# Sheet3.net
KiCad netlist of a schematic drawn in Altium Designer
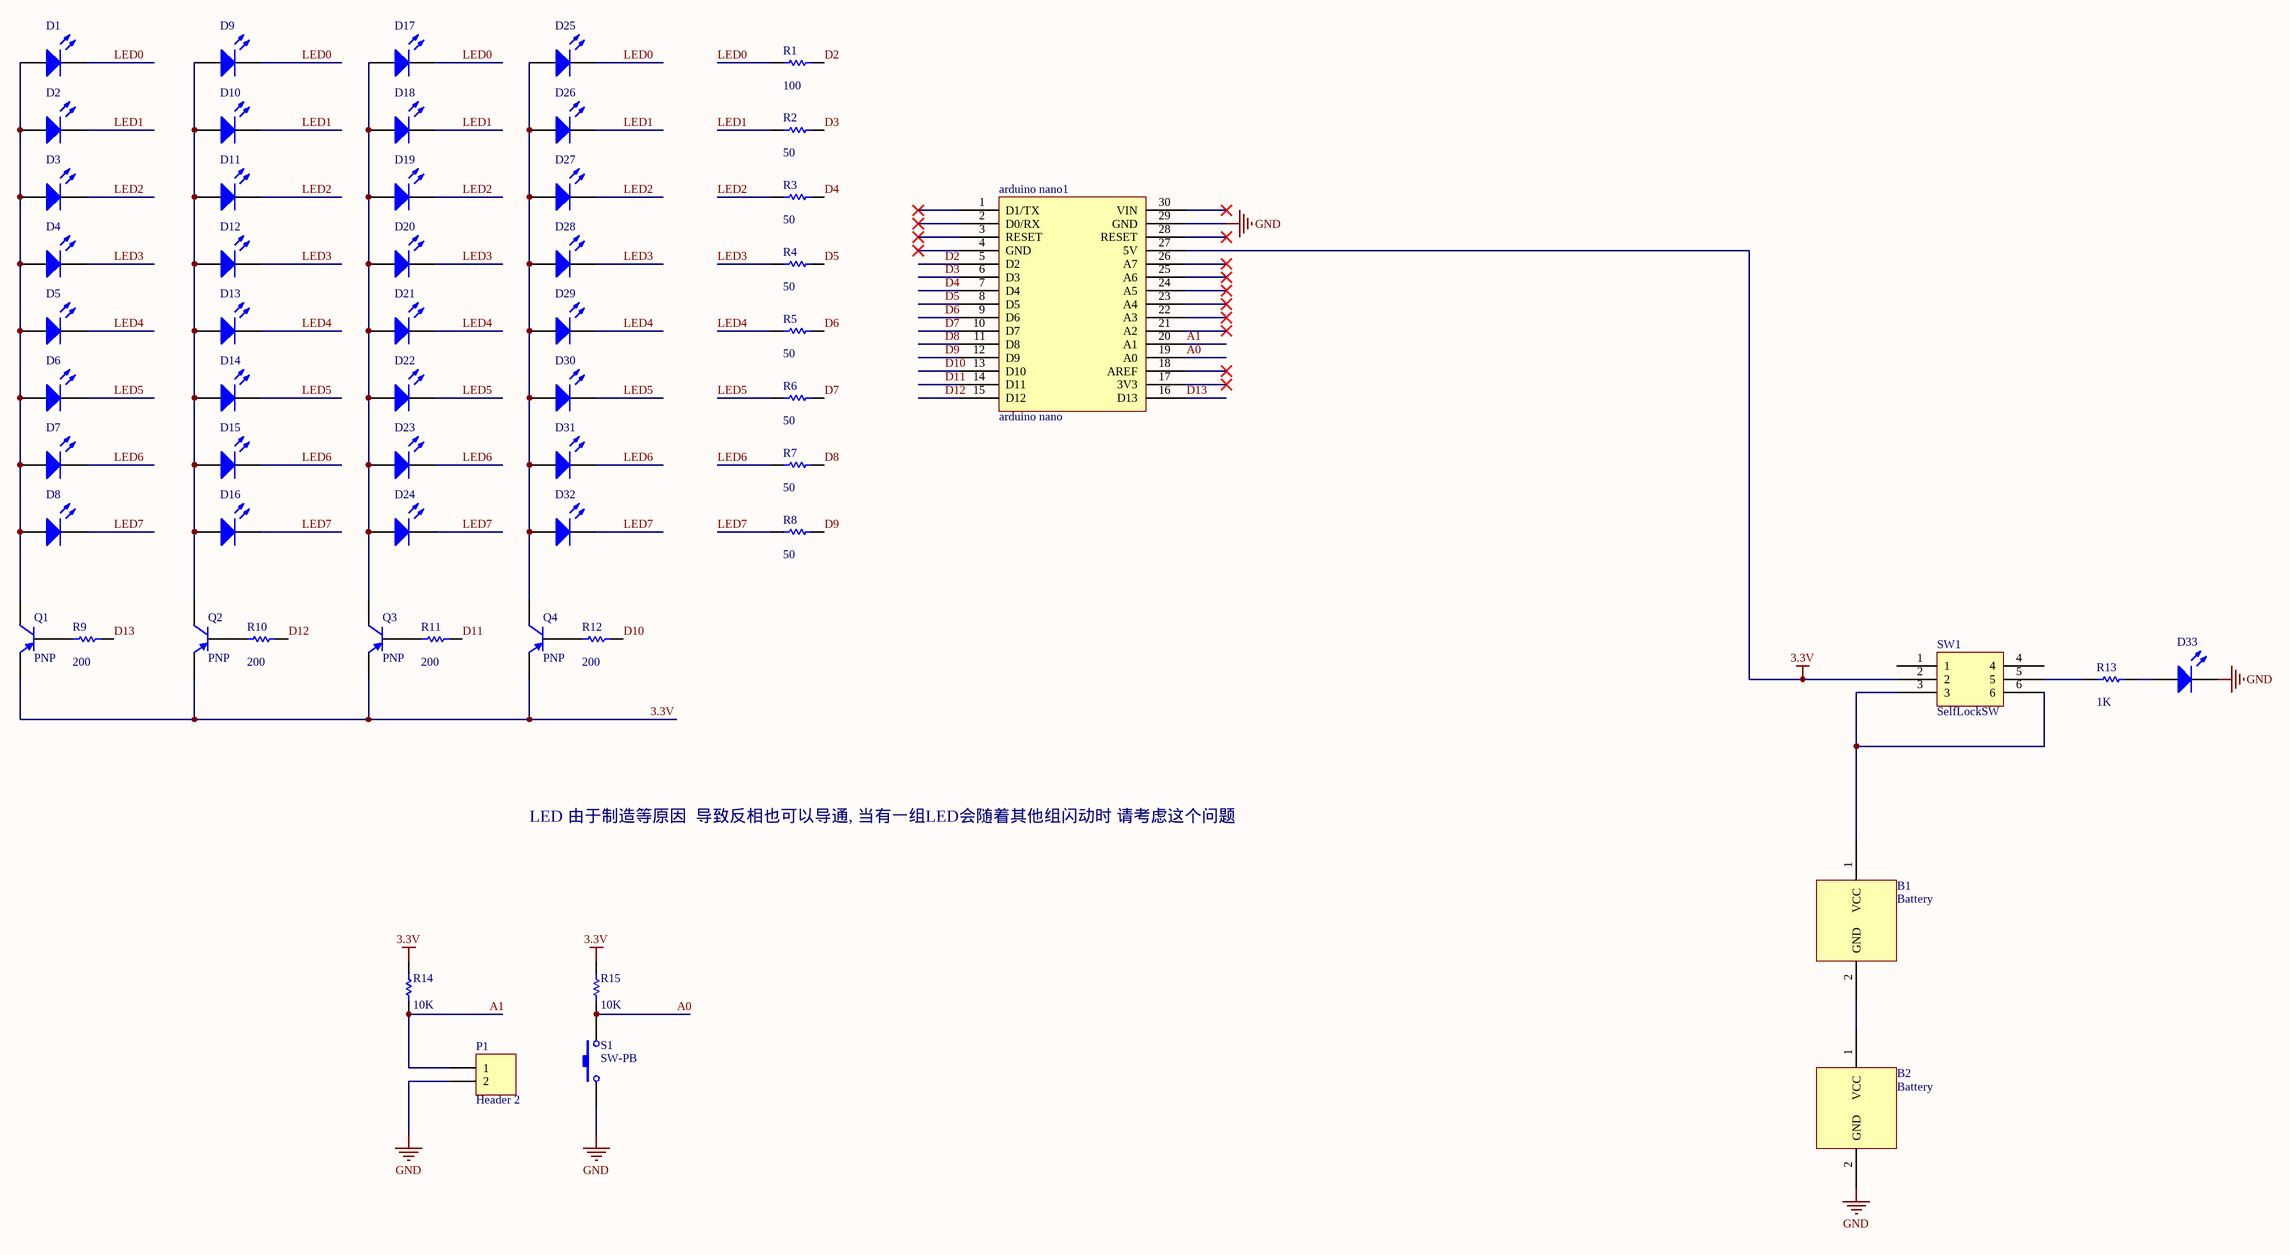
[diagram p0: Sheet3.SchDoc]

(export (version "E")
  (design (tool "Eeschema 10.0.6"))
  (components
    (comp (ref "arduino nano1")
      (value "arduino nano")
      (footprint "PcbLib1:arduino nano - duplicate")
      (libsource (lib "Schlib1") (part "arduino"))
    )
    (comp (ref "B1")
      (value "Battery")
      (footprint "PcbLib1:battery")
      (libsource (lib "Schlib1") (part "Battery"))
    )
    (comp (ref "B2")
      (value "Battery")
      (footprint "PcbLib1:battery")
      (libsource (lib "Schlib1") (part "Battery"))
    )
    (comp (ref "D1")
      (value "LED3")
      (footprint "3.5X2.8X1.9")
      (description "Typical BLUE SiC LED")
      (fields (field (name "PUBLISHER") "Altium Limited"))
      (libsource (lib "Miscellaneous Devices") (part "LED3"))
    )
    (comp (ref "D2")
      (value "LED3")
      (footprint "3.5X2.8X1.9")
      (description "Typical BLUE SiC LED")
      (fields (field (name "PUBLISHER") "Altium Limited"))
      (libsource (lib "Miscellaneous Devices") (part "LED3"))
    )
    (comp (ref "D3")
      (value "LED3")
      (footprint "3.5X2.8X1.9")
      (description "Typical BLUE SiC LED")
      (fields (field (name "PUBLISHER") "Altium Limited"))
      (libsource (lib "Miscellaneous Devices") (part "LED3"))
    )
    (comp (ref "D4")
      (value "LED3")
      (footprint "3.5X2.8X1.9")
      (description "Typical BLUE SiC LED")
      (fields (field (name "PUBLISHER") "Altium Limited"))
      (libsource (lib "Miscellaneous Devices") (part "LED3"))
    )
    (comp (ref "D5")
      (value "LED3")
      (footprint "3.5X2.8X1.9")
      (description "Typical BLUE SiC LED")
      (fields (field (name "PUBLISHER") "Altium Limited"))
      (libsource (lib "Miscellaneous Devices") (part "LED3"))
    )
    (comp (ref "D6")
      (value "LED3")
      (footprint "3.5X2.8X1.9")
      (description "Typical BLUE SiC LED")
      (fields (field (name "PUBLISHER") "Altium Limited"))
      (libsource (lib "Miscellaneous Devices") (part "LED3"))
    )
    (comp (ref "D7")
      (value "LED3")
      (footprint "3.5X2.8X1.9")
      (description "Typical BLUE SiC LED")
      (fields (field (name "PUBLISHER") "Altium Limited"))
      (libsource (lib "Miscellaneous Devices") (part "LED3"))
    )
    (comp (ref "D8")
      (value "LED3")
      (footprint "3.5X2.8X1.9")
      (description "Typical BLUE SiC LED")
      (fields (field (name "PUBLISHER") "Altium Limited"))
      (libsource (lib "Miscellaneous Devices") (part "LED3"))
    )
    (comp (ref "D9")
      (value "LED3")
      (footprint "3.5X2.8X1.9")
      (description "Typical BLUE SiC LED")
      (fields (field (name "PUBLISHER") "Altium Limited"))
      (libsource (lib "Miscellaneous Devices") (part "LED3"))
    )
    (comp (ref "D10")
      (value "LED3")
      (footprint "3.5X2.8X1.9")
      (description "Typical BLUE SiC LED")
      (fields (field (name "PUBLISHER") "Altium Limited"))
      (libsource (lib "Miscellaneous Devices") (part "LED3"))
    )
    (comp (ref "D11")
      (value "LED3")
      (footprint "3.5X2.8X1.9")
      (description "Typical BLUE SiC LED")
      (fields (field (name "PUBLISHER") "Altium Limited"))
      (libsource (lib "Miscellaneous Devices") (part "LED3"))
    )
    (comp (ref "D12")
      (value "LED3")
      (footprint "3.5X2.8X1.9")
      (description "Typical BLUE SiC LED")
      (fields (field (name "PUBLISHER") "Altium Limited"))
      (libsource (lib "Miscellaneous Devices") (part "LED3"))
    )
    (comp (ref "D13")
      (value "LED3")
      (footprint "3.5X2.8X1.9")
      (description "Typical BLUE SiC LED")
      (fields (field (name "PUBLISHER") "Altium Limited"))
      (libsource (lib "Miscellaneous Devices") (part "LED3"))
    )
    (comp (ref "D14")
      (value "LED3")
      (footprint "3.5X2.8X1.9")
      (description "Typical BLUE SiC LED")
      (fields (field (name "PUBLISHER") "Altium Limited"))
      (libsource (lib "Miscellaneous Devices") (part "LED3"))
    )
    (comp (ref "D15")
      (value "LED3")
      (footprint "3.5X2.8X1.9")
      (description "Typical BLUE SiC LED")
      (fields (field (name "PUBLISHER") "Altium Limited"))
      (libsource (lib "Miscellaneous Devices") (part "LED3"))
    )
    (comp (ref "D16")
      (value "LED3")
      (footprint "3.5X2.8X1.9")
      (description "Typical BLUE SiC LED")
      (fields (field (name "PUBLISHER") "Altium Limited"))
      (libsource (lib "Miscellaneous Devices") (part "LED3"))
    )
    (comp (ref "D17")
      (value "LED3")
      (footprint "3.5X2.8X1.9")
      (description "Typical BLUE SiC LED")
      (fields (field (name "PUBLISHER") "Altium Limited"))
      (libsource (lib "Miscellaneous Devices") (part "LED3"))
    )
    (comp (ref "D18")
      (value "LED3")
      (footprint "3.5X2.8X1.9")
      (description "Typical BLUE SiC LED")
      (fields (field (name "PUBLISHER") "Altium Limited"))
      (libsource (lib "Miscellaneous Devices") (part "LED3"))
    )
    (comp (ref "D19")
      (value "LED3")
      (footprint "3.5X2.8X1.9")
      (description "Typical BLUE SiC LED")
      (fields (field (name "PUBLISHER") "Altium Limited"))
      (libsource (lib "Miscellaneous Devices") (part "LED3"))
    )
    (comp (ref "D20")
      (value "LED3")
      (footprint "3.5X2.8X1.9")
      (description "Typical BLUE SiC LED")
      (fields (field (name "PUBLISHER") "Altium Limited"))
      (libsource (lib "Miscellaneous Devices") (part "LED3"))
    )
    (comp (ref "D21")
      (value "LED3")
      (footprint "3.5X2.8X1.9")
      (description "Typical BLUE SiC LED")
      (fields (field (name "PUBLISHER") "Altium Limited"))
      (libsource (lib "Miscellaneous Devices") (part "LED3"))
    )
    (comp (ref "D22")
      (value "LED3")
      (footprint "3.5X2.8X1.9")
      (description "Typical BLUE SiC LED")
      (fields (field (name "PUBLISHER") "Altium Limited"))
      (libsource (lib "Miscellaneous Devices") (part "LED3"))
    )
    (comp (ref "D23")
      (value "LED3")
      (footprint "3.5X2.8X1.9")
      (description "Typical BLUE SiC LED")
      (fields (field (name "PUBLISHER") "Altium Limited"))
      (libsource (lib "Miscellaneous Devices") (part "LED3"))
    )
    (comp (ref "D24")
      (value "LED3")
      (footprint "3.5X2.8X1.9")
      (description "Typical BLUE SiC LED")
      (fields (field (name "PUBLISHER") "Altium Limited"))
      (libsource (lib "Miscellaneous Devices") (part "LED3"))
    )
    (comp (ref "D25")
      (value "LED3")
      (footprint "3.5X2.8X1.9")
      (description "Typical BLUE SiC LED")
      (fields (field (name "PUBLISHER") "Altium Limited"))
      (libsource (lib "Miscellaneous Devices") (part "LED3"))
    )
    (comp (ref "D26")
      (value "LED3")
      (footprint "3.5X2.8X1.9")
      (description "Typical BLUE SiC LED")
      (fields (field (name "PUBLISHER") "Altium Limited"))
      (libsource (lib "Miscellaneous Devices") (part "LED3"))
    )
    (comp (ref "D27")
      (value "LED3")
      (footprint "3.5X2.8X1.9")
      (description "Typical BLUE SiC LED")
      (fields (field (name "PUBLISHER") "Altium Limited"))
      (libsource (lib "Miscellaneous Devices") (part "LED3"))
    )
    (comp (ref "D28")
      (value "LED3")
      (footprint "3.5X2.8X1.9")
      (description "Typical BLUE SiC LED")
      (fields (field (name "PUBLISHER") "Altium Limited"))
      (libsource (lib "Miscellaneous Devices") (part "LED3"))
    )
    (comp (ref "D29")
      (value "LED3")
      (footprint "3.5X2.8X1.9")
      (description "Typical BLUE SiC LED")
      (fields (field (name "PUBLISHER") "Altium Limited"))
      (libsource (lib "Miscellaneous Devices") (part "LED3"))
    )
    (comp (ref "D30")
      (value "LED3")
      (footprint "3.5X2.8X1.9")
      (description "Typical BLUE SiC LED")
      (fields (field (name "PUBLISHER") "Altium Limited"))
      (libsource (lib "Miscellaneous Devices") (part "LED3"))
    )
    (comp (ref "D31")
      (value "LED3")
      (footprint "3.5X2.8X1.9")
      (description "Typical BLUE SiC LED")
      (fields (field (name "PUBLISHER") "Altium Limited"))
      (libsource (lib "Miscellaneous Devices") (part "LED3"))
    )
    (comp (ref "D32")
      (value "LED3")
      (footprint "3.5X2.8X1.9")
      (description "Typical BLUE SiC LED")
      (fields (field (name "PUBLISHER") "Altium Limited"))
      (libsource (lib "Miscellaneous Devices") (part "LED3"))
    )
    (comp (ref "D33")
      (value "LED3")
      (footprint "6-0805_N")
      (description "Typical BLUE SiC LED")
      (fields (field (name "PUBLISHER") "Altium Limited"))
      (libsource (lib "Miscellaneous Devices") (part "LED3"))
    )
    (comp (ref "P1")
      (value "Header 2")
      (footprint "HDR1X2")
      (description "Header, 2-Pin")
      (fields (field (name "PUBLISHER") "Altium Limited"))
      (libsource (lib "Miscellaneous Connectors") (part "Header 2"))
    )
    (comp (ref "Q1")
      (value "PNP")
      (footprint "LC-SOT-23(SOT-23-3):LC-SOT-23(SOT-23-3)")
      (description "PNP Bipolar Transistor")
      (fields (field (name "PUBLISHER") "Altium Limited"))
      (libsource (lib "Miscellaneous Devices") (part "PNP"))
    )
    (comp (ref "Q2")
      (value "PNP")
      (footprint "LC-SOT-23(SOT-23-3):LC-SOT-23(SOT-23-3)")
      (description "PNP Bipolar Transistor")
      (fields (field (name "PUBLISHER") "Altium Limited"))
      (libsource (lib "Miscellaneous Devices") (part "PNP"))
    )
    (comp (ref "Q3")
      (value "PNP")
      (footprint "LC-SOT-23(SOT-23-3):LC-SOT-23(SOT-23-3)")
      (description "PNP Bipolar Transistor")
      (fields (field (name "PUBLISHER") "Altium Limited"))
      (libsource (lib "Miscellaneous Devices") (part "PNP"))
    )
    (comp (ref "Q4")
      (value "PNP")
      (footprint "LC-SOT-23(SOT-23-3):LC-SOT-23(SOT-23-3)")
      (description "PNP Bipolar Transistor")
      (fields (field (name "PUBLISHER") "Altium Limited"))
      (libsource (lib "Miscellaneous Devices") (part "PNP"))
    )
    (comp (ref "R1")
      (value "100")
      (footprint "6-0805_N")
      (description "Resistor")
      (fields (field (name "PUBLISHER") "Altium Limited"))
      (libsource (lib "Miscellaneous Devices") (part "Res1"))
    )
    (comp (ref "R2")
      (value "50")
      (footprint "6-0805_N")
      (description "Resistor")
      (fields (field (name "PUBLISHER") "Altium Limited"))
      (libsource (lib "Miscellaneous Devices") (part "Res1"))
    )
    (comp (ref "R3")
      (value "50")
      (footprint "6-0805_N")
      (description "Resistor")
      (fields (field (name "PUBLISHER") "Altium Limited"))
      (libsource (lib "Miscellaneous Devices") (part "Res1"))
    )
    (comp (ref "R4")
      (value "50")
      (footprint "6-0805_N")
      (description "Resistor")
      (fields (field (name "PUBLISHER") "Altium Limited"))
      (libsource (lib "Miscellaneous Devices") (part "Res1"))
    )
    (comp (ref "R5")
      (value "50")
      (footprint "6-0805_N")
      (description "Resistor")
      (fields (field (name "PUBLISHER") "Altium Limited"))
      (libsource (lib "Miscellaneous Devices") (part "Res1"))
    )
    (comp (ref "R6")
      (value "50")
      (footprint "6-0805_N")
      (description "Resistor")
      (fields (field (name "PUBLISHER") "Altium Limited"))
      (libsource (lib "Miscellaneous Devices") (part "Res1"))
    )
    (comp (ref "R7")
      (value "50")
      (footprint "6-0805_N")
      (description "Resistor")
      (fields (field (name "PUBLISHER") "Altium Limited"))
      (libsource (lib "Miscellaneous Devices") (part "Res1"))
    )
    (comp (ref "R8")
      (value "50")
      (footprint "6-0805_N")
      (description "Resistor")
      (fields (field (name "PUBLISHER") "Altium Limited"))
      (libsource (lib "Miscellaneous Devices") (part "Res1"))
    )
    (comp (ref "R9")
      (value "200")
      (footprint "6-0805_N")
      (description "Resistor")
      (fields (field (name "PUBLISHER") "Altium Limited"))
      (libsource (lib "Miscellaneous Devices") (part "Res1"))
    )
    (comp (ref "R10")
      (value "200")
      (footprint "6-0805_N")
      (description "Resistor")
      (fields (field (name "PUBLISHER") "Altium Limited"))
      (libsource (lib "Miscellaneous Devices") (part "Res1"))
    )
    (comp (ref "R11")
      (value "200")
      (footprint "6-0805_N")
      (description "Resistor")
      (fields (field (name "PUBLISHER") "Altium Limited"))
      (libsource (lib "Miscellaneous Devices") (part "Res1"))
    )
    (comp (ref "R12")
      (value "200")
      (footprint "6-0805_N")
      (description "Resistor")
      (fields (field (name "PUBLISHER") "Altium Limited"))
      (libsource (lib "Miscellaneous Devices") (part "Res1"))
    )
    (comp (ref "R13")
      (value "1K")
      (footprint "6-0805_N")
      (description "Resistor")
      (fields (field (name "PUBLISHER") "Altium Limited"))
      (libsource (lib "Miscellaneous Devices") (part "Res1"))
    )
    (comp (ref "R14")
      (value "10K")
      (footprint "6-0805_N")
      (description "Resistor")
      (fields (field (name "PUBLISHER") "Altium Limited"))
      (libsource (lib "Miscellaneous Devices") (part "Res1"))
    )
    (comp (ref "R15")
      (value "10K")
      (footprint "6-0805_N")
      (description "Resistor")
      (fields (field (name "PUBLISHER") "Altium Limited"))
      (libsource (lib "Miscellaneous Devices") (part "Res1"))
    )
    (comp (ref "S1")
      (value "SW-PB")
      (footprint "Common:贴片开关")
      (description "Switch")
      (fields (field (name "PUBLISHER") "Altium Limited"))
      (libsource (lib "Miscellaneous Devices") (part "SW-PB"))
    )
    (comp (ref "SW1")
      (value "SelfLockSW")
      (footprint "PcbLib1:sw0 - duplicate")
      (libsource (lib "Schlib1") (part "SW0"))
    )
  )
  (nets
    (net (code "1") (name "/A0") (class "Default")
      (node (ref "R15") (pin "1") (pinfunction "1_1") (pintype "passive"))
      (node (ref "S1") (pin "2") (pinfunction "2_2") (pintype "passive"))
      (node (ref "arduino nano1") (pin "19") (pinfunction "A0_19") (pintype "passive"))
    )
    (net (code "2") (name "/A1") (class "Default")
      (node (ref "P1") (pin "1") (pinfunction "1_1") (pintype "passive"))
      (node (ref "R14") (pin "1") (pinfunction "1_1") (pintype "passive"))
      (node (ref "arduino nano1") (pin "20") (pinfunction "A1_20") (pintype "passive"))
    )
    (net (code "3") (name "/D2") (class "Default")
      (node (ref "R1") (pin "2") (pinfunction "2_2") (pintype "passive"))
      (node (ref "arduino nano1") (pin "5") (pinfunction "D2_5") (pintype "passive"))
    )
    (net (code "4") (name "/D3") (class "Default")
      (node (ref "R2") (pin "2") (pinfunction "2_2") (pintype "passive"))
      (node (ref "arduino nano1") (pin "6") (pinfunction "D3_6") (pintype "passive"))
    )
    (net (code "5") (name "/D4") (class "Default")
      (node (ref "R3") (pin "2") (pinfunction "2_2") (pintype "passive"))
      (node (ref "arduino nano1") (pin "7") (pinfunction "D4_7") (pintype "passive"))
    )
    (net (code "6") (name "/D5") (class "Default")
      (node (ref "R4") (pin "2") (pinfunction "2_2") (pintype "passive"))
      (node (ref "arduino nano1") (pin "8") (pinfunction "D5_8") (pintype "passive"))
    )
    (net (code "7") (name "/D6") (class "Default")
      (node (ref "R5") (pin "2") (pinfunction "2_2") (pintype "passive"))
      (node (ref "arduino nano1") (pin "9") (pinfunction "D6_9") (pintype "passive"))
    )
    (net (code "8") (name "/D7") (class "Default")
      (node (ref "R6") (pin "2") (pinfunction "2_2") (pintype "passive"))
      (node (ref "arduino nano1") (pin "10") (pinfunction "D7_10") (pintype "passive"))
    )
    (net (code "9") (name "/D8") (class "Default")
      (node (ref "R7") (pin "2") (pinfunction "2_2") (pintype "passive"))
      (node (ref "arduino nano1") (pin "11") (pinfunction "D8_11") (pintype "passive"))
    )
    (net (code "10") (name "/D9") (class "Default")
      (node (ref "R8") (pin "2") (pinfunction "2_2") (pintype "passive"))
      (node (ref "arduino nano1") (pin "12") (pinfunction "D9_12") (pintype "passive"))
    )
    (net (code "11") (name "/D10") (class "Default")
      (node (ref "R12") (pin "2") (pinfunction "2_2") (pintype "passive"))
      (node (ref "arduino nano1") (pin "13") (pinfunction "D10_13") (pintype "passive"))
    )
    (net (code "12") (name "/D11") (class "Default")
      (node (ref "R11") (pin "2") (pinfunction "2_2") (pintype "passive"))
      (node (ref "arduino nano1") (pin "14") (pinfunction "D11_14") (pintype "passive"))
    )
    (net (code "13") (name "/D12") (class "Default")
      (node (ref "R10") (pin "2") (pinfunction "2_2") (pintype "passive"))
      (node (ref "arduino nano1") (pin "15") (pinfunction "D12_15") (pintype "passive"))
    )
    (net (code "14") (name "/D13") (class "Default")
      (node (ref "R9") (pin "2") (pinfunction "2_2") (pintype "passive"))
      (node (ref "arduino nano1") (pin "16") (pinfunction "D13_16") (pintype "passive"))
    )
    (net (code "15") (name "/LED0") (class "Default")
      (node (ref "D1") (pin "2") (pinfunction "K_2") (pintype "passive"))
      (node (ref "D17") (pin "2") (pinfunction "K_2") (pintype "passive"))
      (node (ref "D25") (pin "2") (pinfunction "K_2") (pintype "passive"))
      (node (ref "D9") (pin "2") (pinfunction "K_2") (pintype "passive"))
      (node (ref "R1") (pin "1") (pinfunction "1_1") (pintype "passive"))
    )
    (net (code "16") (name "/LED1") (class "Default")
      (node (ref "D10") (pin "2") (pinfunction "K_2") (pintype "passive"))
      (node (ref "D18") (pin "2") (pinfunction "K_2") (pintype "passive"))
      (node (ref "D2") (pin "2") (pinfunction "K_2") (pintype "passive"))
      (node (ref "D26") (pin "2") (pinfunction "K_2") (pintype "passive"))
      (node (ref "R2") (pin "1") (pinfunction "1_1") (pintype "passive"))
    )
    (net (code "17") (name "/LED2") (class "Default")
      (node (ref "D11") (pin "2") (pinfunction "K_2") (pintype "passive"))
      (node (ref "D19") (pin "2") (pinfunction "K_2") (pintype "passive"))
      (node (ref "D27") (pin "2") (pinfunction "K_2") (pintype "passive"))
      (node (ref "D3") (pin "2") (pinfunction "K_2") (pintype "passive"))
      (node (ref "R3") (pin "1") (pinfunction "1_1") (pintype "passive"))
    )
    (net (code "18") (name "/LED3") (class "Default")
      (node (ref "D12") (pin "2") (pinfunction "K_2") (pintype "passive"))
      (node (ref "D20") (pin "2") (pinfunction "K_2") (pintype "passive"))
      (node (ref "D28") (pin "2") (pinfunction "K_2") (pintype "passive"))
      (node (ref "D4") (pin "2") (pinfunction "K_2") (pintype "passive"))
      (node (ref "R4") (pin "1") (pinfunction "1_1") (pintype "passive"))
    )
    (net (code "19") (name "/LED4") (class "Default")
      (node (ref "D13") (pin "2") (pinfunction "K_2") (pintype "passive"))
      (node (ref "D21") (pin "2") (pinfunction "K_2") (pintype "passive"))
      (node (ref "D29") (pin "2") (pinfunction "K_2") (pintype "passive"))
      (node (ref "D5") (pin "2") (pinfunction "K_2") (pintype "passive"))
      (node (ref "R5") (pin "1") (pinfunction "1_1") (pintype "passive"))
    )
    (net (code "20") (name "/LED5") (class "Default")
      (node (ref "D14") (pin "2") (pinfunction "K_2") (pintype "passive"))
      (node (ref "D22") (pin "2") (pinfunction "K_2") (pintype "passive"))
      (node (ref "D30") (pin "2") (pinfunction "K_2") (pintype "passive"))
      (node (ref "D6") (pin "2") (pinfunction "K_2") (pintype "passive"))
      (node (ref "R6") (pin "1") (pinfunction "1_1") (pintype "passive"))
    )
    (net (code "21") (name "/LED6") (class "Default")
      (node (ref "D15") (pin "2") (pinfunction "K_2") (pintype "passive"))
      (node (ref "D23") (pin "2") (pinfunction "K_2") (pintype "passive"))
      (node (ref "D31") (pin "2") (pinfunction "K_2") (pintype "passive"))
      (node (ref "D7") (pin "2") (pinfunction "K_2") (pintype "passive"))
      (node (ref "R7") (pin "1") (pinfunction "1_1") (pintype "passive"))
    )
    (net (code "22") (name "/LED7") (class "Default")
      (node (ref "D16") (pin "2") (pinfunction "K_2") (pintype "passive"))
      (node (ref "D24") (pin "2") (pinfunction "K_2") (pintype "passive"))
      (node (ref "D32") (pin "2") (pinfunction "K_2") (pintype "passive"))
      (node (ref "D8") (pin "2") (pinfunction "K_2") (pintype "passive"))
      (node (ref "R8") (pin "1") (pinfunction "1_1") (pintype "passive"))
    )
    (net (code "23") (name "3.3V") (class "Default")
      (node (ref "Q1") (pin "3") (pinfunction "C_3") (pintype "passive"))
      (node (ref "Q2") (pin "3") (pinfunction "C_3") (pintype "passive"))
      (node (ref "Q3") (pin "3") (pinfunction "C_3") (pintype "passive"))
      (node (ref "Q4") (pin "3") (pinfunction "C_3") (pintype "passive"))
      (node (ref "R14") (pin "2") (pinfunction "2_2") (pintype "passive"))
      (node (ref "R15") (pin "2") (pinfunction "2_2") (pintype "passive"))
      (node (ref "SW1") (pin "2") (pinfunction "2_2") (pintype "passive"))
      (node (ref "arduino nano1") (pin "27") (pinfunction "5V_27") (pintype "passive"))
    )
    (net (code "24") (name "GND") (class "Default")
      (node (ref "B2") (pin "2") (pinfunction "GND_2") (pintype "passive"))
      (node (ref "D33") (pin "2") (pinfunction "K_2") (pintype "passive"))
      (node (ref "P1") (pin "2") (pinfunction "2_2") (pintype "passive"))
      (node (ref "S1") (pin "1") (pinfunction "1_1") (pintype "passive"))
      (node (ref "arduino nano1") (pin "29") (pinfunction "GND_29") (pintype "passive"))
    )
    (net (code "25") (name "Net-(B1-GND)") (class "Default")
      (node (ref "B1") (pin "2") (pinfunction "GND_2") (pintype "passive"))
      (node (ref "B2") (pin "1") (pinfunction "VCC_1") (pintype "passive"))
    )
    (net (code "26") (name "Net-(B1-VCC)") (class "Default")
      (node (ref "B1") (pin "1") (pinfunction "VCC_1") (pintype "passive"))
      (node (ref "SW1") (pin "3") (pinfunction "3_3") (pintype "passive"))
      (node (ref "SW1") (pin "6") (pinfunction "6_6") (pintype "passive"))
    )
    (net (code "27") (name "Net-(D1-A)") (class "Default")
      (node (ref "D1") (pin "1") (pinfunction "A_1") (pintype "passive"))
      (node (ref "D2") (pin "1") (pinfunction "A_1") (pintype "passive"))
      (node (ref "D3") (pin "1") (pinfunction "A_1") (pintype "passive"))
      (node (ref "D4") (pin "1") (pinfunction "A_1") (pintype "passive"))
      (node (ref "D5") (pin "1") (pinfunction "A_1") (pintype "passive"))
      (node (ref "D6") (pin "1") (pinfunction "A_1") (pintype "passive"))
      (node (ref "D7") (pin "1") (pinfunction "A_1") (pintype "passive"))
      (node (ref "D8") (pin "1") (pinfunction "A_1") (pintype "passive"))
      (node (ref "Q1") (pin "1") (pinfunction "B_1") (pintype "passive"))
    )
    (net (code "28") (name "Net-(D10-A)") (class "Default")
      (node (ref "D10") (pin "1") (pinfunction "A_1") (pintype "passive"))
      (node (ref "D11") (pin "1") (pinfunction "A_1") (pintype "passive"))
      (node (ref "D12") (pin "1") (pinfunction "A_1") (pintype "passive"))
      (node (ref "D13") (pin "1") (pinfunction "A_1") (pintype "passive"))
      (node (ref "D14") (pin "1") (pinfunction "A_1") (pintype "passive"))
      (node (ref "D15") (pin "1") (pinfunction "A_1") (pintype "passive"))
      (node (ref "D16") (pin "1") (pinfunction "A_1") (pintype "passive"))
      (node (ref "D9") (pin "1") (pinfunction "A_1") (pintype "passive"))
      (node (ref "Q2") (pin "1") (pinfunction "B_1") (pintype "passive"))
    )
    (net (code "29") (name "Net-(D17-A)") (class "Default")
      (node (ref "D17") (pin "1") (pinfunction "A_1") (pintype "passive"))
      (node (ref "D18") (pin "1") (pinfunction "A_1") (pintype "passive"))
      (node (ref "D19") (pin "1") (pinfunction "A_1") (pintype "passive"))
      (node (ref "D20") (pin "1") (pinfunction "A_1") (pintype "passive"))
      (node (ref "D21") (pin "1") (pinfunction "A_1") (pintype "passive"))
      (node (ref "D22") (pin "1") (pinfunction "A_1") (pintype "passive"))
      (node (ref "D23") (pin "1") (pinfunction "A_1") (pintype "passive"))
      (node (ref "D24") (pin "1") (pinfunction "A_1") (pintype "passive"))
      (node (ref "Q3") (pin "1") (pinfunction "B_1") (pintype "passive"))
    )
    (net (code "30") (name "Net-(D25-A)") (class "Default")
      (node (ref "D25") (pin "1") (pinfunction "A_1") (pintype "passive"))
      (node (ref "D26") (pin "1") (pinfunction "A_1") (pintype "passive"))
      (node (ref "D27") (pin "1") (pinfunction "A_1") (pintype "passive"))
      (node (ref "D28") (pin "1") (pinfunction "A_1") (pintype "passive"))
      (node (ref "D29") (pin "1") (pinfunction "A_1") (pintype "passive"))
      (node (ref "D30") (pin "1") (pinfunction "A_1") (pintype "passive"))
      (node (ref "D31") (pin "1") (pinfunction "A_1") (pintype "passive"))
      (node (ref "D32") (pin "1") (pinfunction "A_1") (pintype "passive"))
      (node (ref "Q4") (pin "1") (pinfunction "B_1") (pintype "passive"))
    )
    (net (code "31") (name "Net-(D33-A)") (class "Default")
      (node (ref "D33") (pin "1") (pinfunction "A_1") (pintype "passive"))
      (node (ref "R13") (pin "1") (pinfunction "1_1") (pintype "passive"))
    )
    (net (code "32") (name "Net-(Q1-E)") (class "Default")
      (node (ref "Q1") (pin "2") (pinfunction "E_2") (pintype "passive"))
      (node (ref "R9") (pin "1") (pinfunction "1_1") (pintype "passive"))
    )
    (net (code "33") (name "Net-(Q2-E)") (class "Default")
      (node (ref "Q2") (pin "2") (pinfunction "E_2") (pintype "passive"))
      (node (ref "R10") (pin "1") (pinfunction "1_1") (pintype "passive"))
    )
    (net (code "34") (name "Net-(Q3-E)") (class "Default")
      (node (ref "Q3") (pin "2") (pinfunction "E_2") (pintype "passive"))
      (node (ref "R11") (pin "1") (pinfunction "1_1") (pintype "passive"))
    )
    (net (code "35") (name "Net-(Q4-E)") (class "Default")
      (node (ref "Q4") (pin "2") (pinfunction "E_2") (pintype "passive"))
      (node (ref "R12") (pin "1") (pinfunction "1_1") (pintype "passive"))
    )
    (net (code "36") (name "Net-(R13-Pad2)") (class "Default")
      (node (ref "R13") (pin "2") (pinfunction "2_2") (pintype "passive"))
      (node (ref "SW1") (pin "5") (pinfunction "5_5") (pintype "passive"))
    )
    (net (code "37") (name "unconnected-(SW1-Pad1)") (class "Default")
      (node (ref "SW1") (pin "1") (pinfunction "1_1") (pintype "passive"))
    )
    (net (code "38") (name "unconnected-(SW1-Pad4)") (class "Default")
      (node (ref "SW1") (pin "4") (pinfunction "4_4") (pintype "passive"))
    )
    (net (code "39") (name "unconnected-(arduino nano1-3V3-Pad17)") (class "Default")
      (node (ref "arduino nano1") (pin "17") (pinfunction "3V3_17") (pintype "passive+no_connect"))
    )
    (net (code "40") (name "unconnected-(arduino nano1-A2-Pad21)") (class "Default")
      (node (ref "arduino nano1") (pin "21") (pinfunction "A2_21") (pintype "passive+no_connect"))
    )
    (net (code "41") (name "unconnected-(arduino nano1-A3-Pad22)") (class "Default")
      (node (ref "arduino nano1") (pin "22") (pinfunction "A3_22") (pintype "passive+no_connect"))
    )
    (net (code "42") (name "unconnected-(arduino nano1-A4-Pad23)") (class "Default")
      (node (ref "arduino nano1") (pin "23") (pinfunction "A4_23") (pintype "passive+no_connect"))
    )
    (net (code "43") (name "unconnected-(arduino nano1-A5-Pad24)") (class "Default")
      (node (ref "arduino nano1") (pin "24") (pinfunction "A5_24") (pintype "passive+no_connect"))
    )
    (net (code "44") (name "unconnected-(arduino nano1-A6-Pad25)") (class "Default")
      (node (ref "arduino nano1") (pin "25") (pinfunction "A6_25") (pintype "passive+no_connect"))
    )
    (net (code "45") (name "unconnected-(arduino nano1-A7-Pad26)") (class "Default")
      (node (ref "arduino nano1") (pin "26") (pinfunction "A7_26") (pintype "passive+no_connect"))
    )
    (net (code "46") (name "unconnected-(arduino nano1-AREF-Pad18)") (class "Default")
      (node (ref "arduino nano1") (pin "18") (pinfunction "AREF_18") (pintype "passive+no_connect"))
    )
    (net (code "47") (name "unconnected-(arduino nano1-D0{slash}RX-Pad2)") (class "Default")
      (node (ref "arduino nano1") (pin "2") (pinfunction "D0/RX_2") (pintype "passive+no_connect"))
    )
    (net (code "48") (name "unconnected-(arduino nano1-D1{slash}TX-Pad1)") (class "Default")
      (node (ref "arduino nano1") (pin "1") (pinfunction "D1/TX_1") (pintype "passive+no_connect"))
    )
    (net (code "49") (name "unconnected-(arduino nano1-GND-Pad4)") (class "Default")
      (node (ref "arduino nano1") (pin "4") (pinfunction "GND_4") (pintype "passive+no_connect"))
    )
    (net (code "50") (name "unconnected-(arduino nano1-RESET-Pad3)") (class "Default")
      (node (ref "arduino nano1") (pin "3") (pinfunction "RESET_3") (pintype "passive+no_connect"))
    )
    (net (code "51") (name "unconnected-(arduino nano1-RESET-Pad28)") (class "Default")
      (node (ref "arduino nano1") (pin "28") (pinfunction "RESET_28") (pintype "passive+no_connect"))
    )
    (net (code "52") (name "unconnected-(arduino nano1-VIN-Pad30)") (class "Default")
      (node (ref "arduino nano1") (pin "30") (pinfunction "VIN_30") (pintype "passive+no_connect"))
    )
  )
)
